# control_board_V2.net
KiCad netlist of a schematic drawn in EAGLE
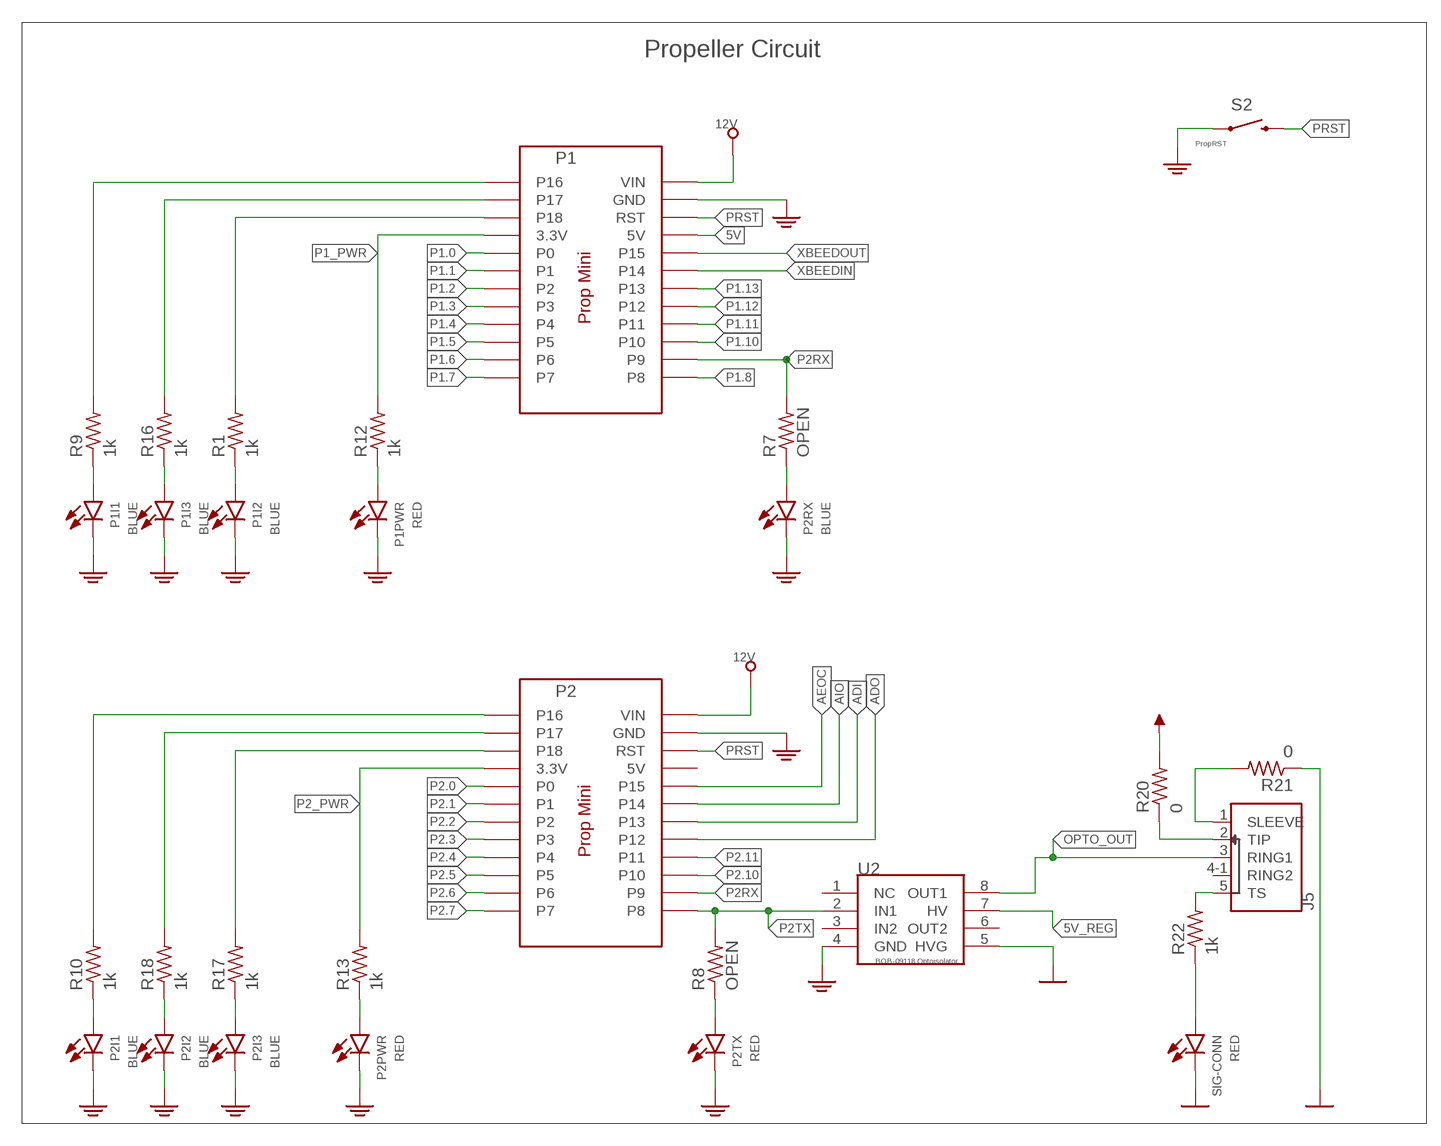
[diagram p0: schematic, sheet 1, part 1 of 2]
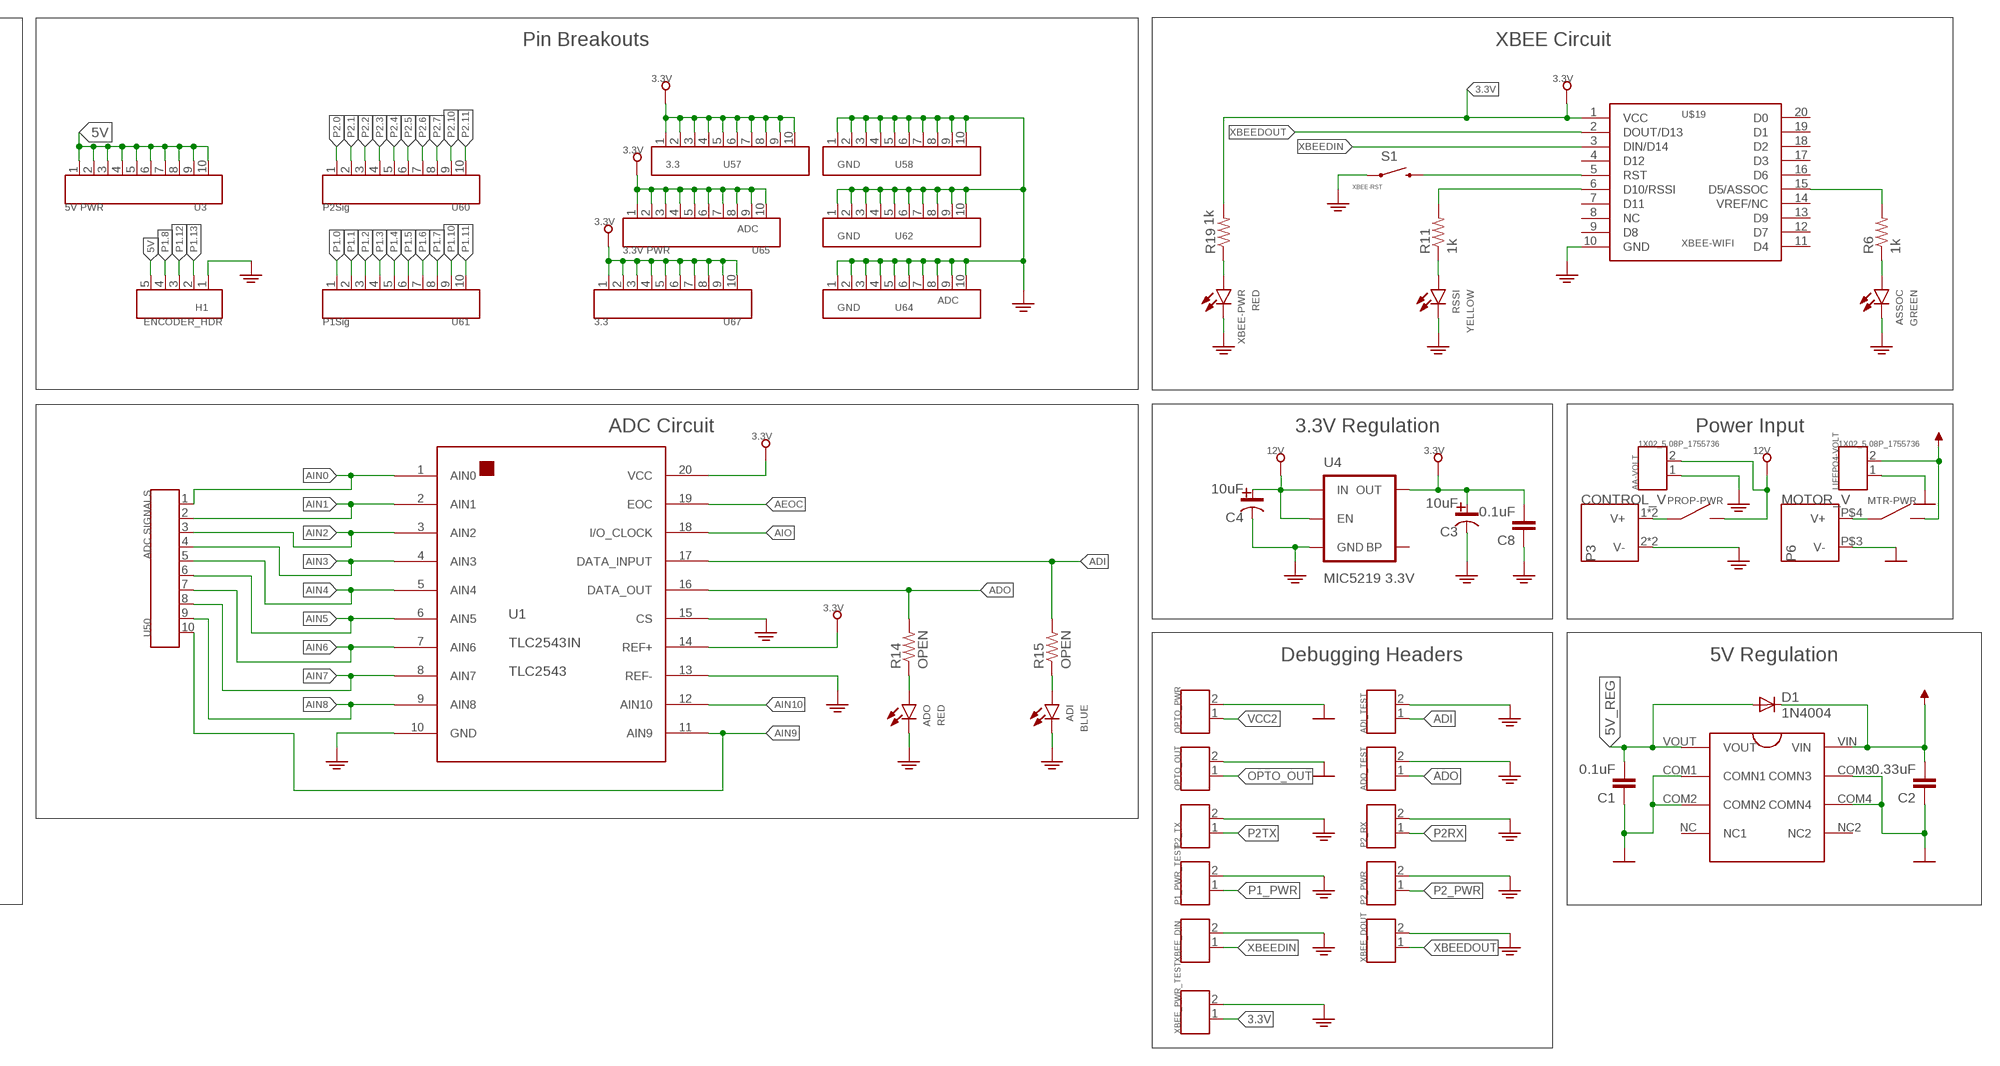
[diagram p1: schematic, sheet 1, part 2 of 2]

(export (version "E")
  (design (tool "Eeschema 10.0.6"))
  (components
    (comp (ref "AA-VOLT")
      (value "1X02_5.08P_1755736")
      (footprint "eagle-import:DIP5.08MM-1X02")
      (libsource (lib "eagle-import") (part "1X02_5.08P_1755736"))
    )
    (comp (ref "ADI")
      (value "BLUE")
      (footprint "eagle-import:0603")
      (libsource (lib "eagle-import") (part "LED-STD"))
    )
    (comp (ref "ADI_TEST")
      (value "1X02")
      (footprint "eagle-import:DIP0.1-1X02")
      (libsource (lib "eagle-import") (part "1X02"))
    )
    (comp (ref "ADO")
      (value "RED")
      (footprint "eagle-import:0603")
      (libsource (lib "eagle-import") (part "LED-STD"))
    )
    (comp (ref "ADO_TEST")
      (value "1X02")
      (footprint "eagle-import:DIP0.1-1X02")
      (libsource (lib "eagle-import") (part "1X02"))
    )
    (comp (ref "ASSOC")
      (value "GREEN")
      (footprint "eagle-import:0603")
      (libsource (lib "eagle-import") (part "LED-STD"))
    )
    (comp (ref "C1")
      (value "0.1uF")
      (footprint "eagle-import:0603")
      (libsource (lib "eagle-import") (part "C0603"))
    )
    (comp (ref "C2")
      (value "0.33uF")
      (footprint "eagle-import:0603")
      (libsource (lib "eagle-import") (part "C0603"))
    )
    (comp (ref "C3")
      (value "10uF")
      (footprint "eagle-import:0603-POL")
      (libsource (lib "eagle-import") (part "C-POL-T"))
    )
    (comp (ref "C4")
      (value "10uF")
      (footprint "eagle-import:0603-POL")
      (libsource (lib "eagle-import") (part "C-POL-T"))
    )
    (comp (ref "C8")
      (value "0.1uF")
      (footprint "eagle-import:0603")
      (libsource (lib "eagle-import") (part "C0603"))
    )
    (comp (ref "D1")
      (value "1N4004")
      (footprint "eagle-import:DO41-10")
      (libsource (lib "eagle-import") (part "1N4004"))
    )
    (comp (ref "H1")
      (value "ENCODER_HDR")
      (footprint "eagle-import:DIP0.1-1X05")
      (libsource (lib "eagle-import") (part "1X05"))
    )
    (comp (ref "J5")
      (value "SJ1-42535TS")
      (footprint "eagle-import:SJ1-42534-SMT")
      (libsource (lib "eagle-import") (part "SJ1-42535TS"))
    )
    (comp (ref "LIFEPO4-VOLT")
      (value "1X02_5.08P_1755736")
      (footprint "eagle-import:DIP5.08MM-1X02")
      (libsource (lib "eagle-import") (part "1X02_5.08P_1755736"))
    )
    (comp (ref "MTR-PWR")
      (value "A11JP")
      (footprint "eagle-import:NKK-SP-ASERIES")
      (libsource (lib "eagle-import") (part "A11JP"))
    )
    (comp (ref "OPTO_OUT")
      (value "1X02")
      (footprint "eagle-import:DIP0.1-1X02")
      (libsource (lib "eagle-import") (part "1X02"))
    )
    (comp (ref "OPTO_PWR")
      (value "1X02")
      (footprint "eagle-import:DIP0.1-1X02")
      (libsource (lib "eagle-import") (part "1X02"))
    )
    (comp (ref "P1")
      (value "PROP-MINI")
      (footprint "eagle-import:PROP-MINI")
      (libsource (lib "eagle-import") (part "PROP-MINI"))
    )
    (comp (ref "P1I1")
      (value "BLUE")
      (footprint "eagle-import:0603")
      (libsource (lib "eagle-import") (part "LED-STD"))
    )
    (comp (ref "P1I2")
      (value "BLUE")
      (footprint "eagle-import:0603")
      (libsource (lib "eagle-import") (part "LED-STD"))
    )
    (comp (ref "P1I3")
      (value "BLUE")
      (footprint "eagle-import:0603")
      (libsource (lib "eagle-import") (part "LED-STD"))
    )
    (comp (ref "P1PWR")
      (value "RED")
      (footprint "eagle-import:0603")
      (libsource (lib "eagle-import") (part "LED-STD"))
    )
    (comp (ref "P1_PWR_TEST")
      (value "1X02")
      (footprint "eagle-import:DIP0.1-1X02")
      (libsource (lib "eagle-import") (part "1X02"))
    )
    (comp (ref "P2")
      (value "PROP-MINI")
      (footprint "eagle-import:PROP-MINI")
      (libsource (lib "eagle-import") (part "PROP-MINI"))
    )
    (comp (ref "P2I1")
      (value "BLUE")
      (footprint "eagle-import:0603")
      (libsource (lib "eagle-import") (part "LED-STD"))
    )
    (comp (ref "P2I2")
      (value "BLUE")
      (footprint "eagle-import:0603")
      (libsource (lib "eagle-import") (part "LED-STD"))
    )
    (comp (ref "P2I3")
      (value "BLUE")
      (footprint "eagle-import:0603")
      (libsource (lib "eagle-import") (part "LED-STD"))
    )
    (comp (ref "P2PWR")
      (value "RED")
      (footprint "eagle-import:0603")
      (libsource (lib "eagle-import") (part "LED-STD"))
    )
    (comp (ref "P2RX")
      (value "BLUE")
      (footprint "eagle-import:0603")
      (libsource (lib "eagle-import") (part "LED-STD"))
    )
    (comp (ref "P2TX")
      (value "RED")
      (footprint "eagle-import:0603")
      (libsource (lib "eagle-import") (part "LED-STD"))
    )
    (comp (ref "P2_PWR")
      (value "1X02")
      (footprint "eagle-import:DIP0.1-1X02")
      (libsource (lib "eagle-import") (part "1X02"))
    )
    (comp (ref "P2_RX")
      (value "1X02")
      (footprint "eagle-import:DIP0.1-1X02")
      (libsource (lib "eagle-import") (part "1X02"))
    )
    (comp (ref "P2_TX")
      (value "1X02")
      (footprint "eagle-import:DIP0.1-1X02")
      (libsource (lib "eagle-import") (part "1X02"))
    )
    (comp (ref "P3")
      (value "CONTROL_V")
      (footprint "eagle-import:PJ-002BH-SMT-TR")
      (libsource (lib "eagle-import") (part "SINGLE-LINEPJ-014DH-SMT"))
    )
    (comp (ref "P6")
      (value "MOTOR_V")
      (footprint "eagle-import:PJ-037A")
      (libsource (lib "eagle-import") (part "SINGLE-LINE'"))
    )
    (comp (ref "PROP-PWR")
      (value "A11JP")
      (footprint "eagle-import:NKK-SP-ASERIES")
      (libsource (lib "eagle-import") (part "A11JP"))
    )
    (comp (ref "R1")
      (value "1k")
      (footprint "eagle-import:0603")
      (libsource (lib "eagle-import") (part "R0603"))
    )
    (comp (ref "R6")
      (value "1k")
      (footprint "eagle-import:0603")
      (libsource (lib "eagle-import") (part "R0603"))
    )
    (comp (ref "R7")
      (value "OPEN")
      (footprint "eagle-import:0603")
      (libsource (lib "eagle-import") (part "R0603"))
    )
    (comp (ref "R8")
      (value "OPEN")
      (footprint "eagle-import:0603")
      (libsource (lib "eagle-import") (part "R0603"))
    )
    (comp (ref "R9")
      (value "1k")
      (footprint "eagle-import:0603")
      (libsource (lib "eagle-import") (part "R0603"))
    )
    (comp (ref "R10")
      (value "1k")
      (footprint "eagle-import:0603")
      (libsource (lib "eagle-import") (part "R0603"))
    )
    (comp (ref "R11")
      (value "1k")
      (footprint "eagle-import:0603")
      (libsource (lib "eagle-import") (part "R0603"))
    )
    (comp (ref "R12")
      (value "1k")
      (footprint "eagle-import:0603")
      (libsource (lib "eagle-import") (part "R0603"))
    )
    (comp (ref "R13")
      (value "1k")
      (footprint "eagle-import:0603")
      (libsource (lib "eagle-import") (part "R0603"))
    )
    (comp (ref "R14")
      (value "OPEN")
      (footprint "eagle-import:0603")
      (libsource (lib "eagle-import") (part "R0603"))
    )
    (comp (ref "R15")
      (value "OPEN")
      (footprint "eagle-import:0603")
      (libsource (lib "eagle-import") (part "R0603"))
    )
    (comp (ref "R16")
      (value "1k")
      (footprint "eagle-import:0603")
      (libsource (lib "eagle-import") (part "R0603"))
    )
    (comp (ref "R17")
      (value "1k")
      (footprint "eagle-import:0603")
      (libsource (lib "eagle-import") (part "R0603"))
    )
    (comp (ref "R18")
      (value "1k")
      (footprint "eagle-import:0603")
      (libsource (lib "eagle-import") (part "R0603"))
    )
    (comp (ref "R19")
      (value "1k")
      (footprint "eagle-import:0603")
      (libsource (lib "eagle-import") (part "R0603"))
    )
    (comp (ref "R20")
      (value "0")
      (footprint "eagle-import:0603")
      (libsource (lib "eagle-import") (part "R0603"))
    )
    (comp (ref "R21")
      (value "0")
      (footprint "eagle-import:0603")
      (libsource (lib "eagle-import") (part "R0603"))
    )
    (comp (ref "R22")
      (value "1k")
      (footprint "eagle-import:0603")
      (libsource (lib "eagle-import") (part "R0603"))
    )
    (comp (ref "RSSI")
      (value "YELLOW")
      (footprint "eagle-import:0603")
      (libsource (lib "eagle-import") (part "LED-STD"))
    )
    (comp (ref "S1")
      (value "XBEE-RST")
      (footprint "eagle-import:TACTILE_SWITCH_SMD-2")
      (libsource (lib "eagle-import") (part "SWITCH-MOMENTARY-2SMD-2"))
    )
    (comp (ref "S2")
      (value "PropRST")
      (footprint "eagle-import:TACTILE_SWITCH_SMD-2")
      (libsource (lib "eagle-import") (part "SWITCH-MOMENTARY-2SMD-2"))
    )
    (comp (ref "SIG-CONN")
      (value "RED")
      (footprint "eagle-import:0603")
      (libsource (lib "eagle-import") (part "LED-STD"))
    )
    (comp (ref "U$19")
      (value "XBEE-WIFI")
      (footprint "eagle-import:XBEE-STD")
      (libsource (lib "eagle-import") (part "XBEE-WIFI"))
    )
    (comp (ref "U1")
      (value "TLC2543IN")
      (footprint "eagle-import:DIL-20")
      (libsource (lib "eagle-import") (part "TLC2543IN"))
    )
    (comp (ref "U2")
      (value "BOB-09118")
      (footprint "eagle-import:DIL08-0.1P-6W")
      (libsource (lib "eagle-import") (part "BOB-09118"))
    )
    (comp (ref "U3")
      (value "5V PWR")
      (footprint "eagle-import:DIP0.1-1X10")
      (libsource (lib "eagle-import") (part "1X10"))
    )
    (comp (ref "U4")
      (value "MIC5219 3.3V")
      (footprint "eagle-import:SOT23-5")
      (libsource (lib "eagle-import") (part "V_REG_MIC52193.3V"))
    )
    (comp (ref "U50")
      (value "ADC SIGNALS")
      (footprint "eagle-import:DIP0.1-1X10")
      (libsource (lib "eagle-import") (part "1X10"))
    )
    (comp (ref "U57")
      (value "3.3")
      (footprint "eagle-import:DIP0.1-1X10")
      (libsource (lib "eagle-import") (part "1X10"))
    )
    (comp (ref "U58")
      (value "GND")
      (footprint "eagle-import:DIP0.1-1X10")
      (libsource (lib "eagle-import") (part "1X10"))
    )
    (comp (ref "U60")
      (value "P2Sig")
      (footprint "eagle-import:DIP0.1-1X10")
      (libsource (lib "eagle-import") (part "1X10"))
    )
    (comp (ref "U61")
      (value "P1Sig")
      (footprint "eagle-import:DIP0.1-1X10")
      (libsource (lib "eagle-import") (part "1X10"))
    )
    (comp (ref "U62")
      (value "GND")
      (footprint "eagle-import:DIP0.1-1X10")
      (libsource (lib "eagle-import") (part "1X10"))
    )
    (comp (ref "U64")
      (value "GND")
      (footprint "eagle-import:DIP0.1-1X10")
      (libsource (lib "eagle-import") (part "1X10"))
    )
    (comp (ref "U65")
      (value "3.3V PWR")
      (footprint "eagle-import:DIP0.1-1X10")
      (libsource (lib "eagle-import") (part "1X10"))
    )
    (comp (ref "U67")
      (value "3.3")
      (footprint "eagle-import:DIP0.1-1X10")
      (libsource (lib "eagle-import") (part "1X10"))
    )
    (comp (ref "U70")
      (value "R-PDSO-G8")
      (footprint "eagle-import:UA78L05ACDR")
      (libsource (lib "eagle-import") (part "R-PDSO-G8"))
    )
    (comp (ref "XBEE-PWR")
      (value "RED")
      (footprint "eagle-import:0603")
      (libsource (lib "eagle-import") (part "LED-STD"))
    )
    (comp (ref "XBEE_DIN")
      (value "1X02")
      (footprint "eagle-import:DIP0.1-1X02")
      (libsource (lib "eagle-import") (part "1X02"))
    )
    (comp (ref "XBEE_DOUT")
      (value "1X02")
      (footprint "eagle-import:DIP0.1-1X02")
      (libsource (lib "eagle-import") (part "1X02"))
    )
    (comp (ref "XBEE_PWR_TEST")
      (value "1X02")
      (footprint "eagle-import:DIP0.1-1X02")
      (libsource (lib "eagle-import") (part "1X02"))
    )
  )
  (nets
    (net (code "1") (name "3.3V") (class "Default")
      (node (ref "C3") (pin "2") (pinfunction "2_2") (pintype "passive"))
      (node (ref "C8") (pin "2") (pinfunction "2_2") (pintype "passive"))
      (node (ref "R19") (pin "2") (pinfunction "P$2_2") (pintype "bidirectional"))
      (node (ref "U$19") (pin "1") (pinfunction "VCC_1") (pintype "bidirectional"))
      (node (ref "U1") (pin "14") (pinfunction "REF+_14") (pintype "bidirectional"))
      (node (ref "U1") (pin "20") (pinfunction "VCC_20") (pintype "bidirectional"))
      (node (ref "U4") (pin "5") (pinfunction "OUT_5") (pintype "passive"))
      (node (ref "U57") (pin "1") (pinfunction "1_1") (pintype "bidirectional"))
      (node (ref "U57") (pin "10") (pinfunction "10_10") (pintype "bidirectional"))
      (node (ref "U57") (pin "2") (pinfunction "2_2") (pintype "bidirectional"))
      (node (ref "U57") (pin "3") (pinfunction "3_3") (pintype "bidirectional"))
      (node (ref "U57") (pin "4") (pinfunction "4_4") (pintype "bidirectional"))
      (node (ref "U57") (pin "5") (pinfunction "5_5") (pintype "bidirectional"))
      (node (ref "U57") (pin "6") (pinfunction "6_6") (pintype "bidirectional"))
      (node (ref "U57") (pin "7") (pinfunction "7_7") (pintype "bidirectional"))
      (node (ref "U57") (pin "8") (pinfunction "8_8") (pintype "bidirectional"))
      (node (ref "U57") (pin "9") (pinfunction "9_9") (pintype "bidirectional"))
      (node (ref "U65") (pin "1") (pinfunction "1_1") (pintype "bidirectional"))
      (node (ref "U65") (pin "10") (pinfunction "10_10") (pintype "bidirectional"))
      (node (ref "U65") (pin "2") (pinfunction "2_2") (pintype "bidirectional"))
      (node (ref "U65") (pin "3") (pinfunction "3_3") (pintype "bidirectional"))
      (node (ref "U65") (pin "4") (pinfunction "4_4") (pintype "bidirectional"))
      (node (ref "U65") (pin "5") (pinfunction "5_5") (pintype "bidirectional"))
      (node (ref "U65") (pin "6") (pinfunction "6_6") (pintype "bidirectional"))
      (node (ref "U65") (pin "7") (pinfunction "7_7") (pintype "bidirectional"))
      (node (ref "U65") (pin "8") (pinfunction "8_8") (pintype "bidirectional"))
      (node (ref "U65") (pin "9") (pinfunction "9_9") (pintype "bidirectional"))
      (node (ref "U67") (pin "1") (pinfunction "1_1") (pintype "bidirectional"))
      (node (ref "U67") (pin "10") (pinfunction "10_10") (pintype "bidirectional"))
      (node (ref "U67") (pin "2") (pinfunction "2_2") (pintype "bidirectional"))
      (node (ref "U67") (pin "3") (pinfunction "3_3") (pintype "bidirectional"))
      (node (ref "U67") (pin "4") (pinfunction "4_4") (pintype "bidirectional"))
      (node (ref "U67") (pin "5") (pinfunction "5_5") (pintype "bidirectional"))
      (node (ref "U67") (pin "6") (pinfunction "6_6") (pintype "bidirectional"))
      (node (ref "U67") (pin "7") (pinfunction "7_7") (pintype "bidirectional"))
      (node (ref "U67") (pin "8") (pinfunction "8_8") (pintype "bidirectional"))
      (node (ref "U67") (pin "9") (pinfunction "9_9") (pintype "bidirectional"))
      (node (ref "XBEE_PWR_TEST") (pin "1") (pinfunction "1_1") (pintype "bidirectional"))
    )
    (net (code "2") (name "5V") (class "Default")
      (node (ref "H1") (pin "5") (pinfunction "5_5") (pintype "bidirectional"))
      (node (ref "P1") (pin "5V") (pinfunction "5V_5V") (pintype "bidirectional"))
      (node (ref "U3") (pin "1") (pinfunction "1_1") (pintype "bidirectional"))
      (node (ref "U3") (pin "10") (pinfunction "10_10") (pintype "bidirectional"))
      (node (ref "U3") (pin "2") (pinfunction "2_2") (pintype "bidirectional"))
      (node (ref "U3") (pin "3") (pinfunction "3_3") (pintype "bidirectional"))
      (node (ref "U3") (pin "4") (pinfunction "4_4") (pintype "bidirectional"))
      (node (ref "U3") (pin "5") (pinfunction "5_5") (pintype "bidirectional"))
      (node (ref "U3") (pin "6") (pinfunction "6_6") (pintype "bidirectional"))
      (node (ref "U3") (pin "7") (pinfunction "7_7") (pintype "bidirectional"))
      (node (ref "U3") (pin "8") (pinfunction "8_8") (pintype "bidirectional"))
      (node (ref "U3") (pin "9") (pinfunction "9_9") (pintype "bidirectional"))
    )
    (net (code "3") (name "5V_REG") (class "Default")
      (node (ref "C1") (pin "2") (pinfunction "2_2") (pintype "passive"))
      (node (ref "D1") (pin "A") (pinfunction "A_A") (pintype "passive"))
      (node (ref "U2") (pin "7") (pinfunction "HV_7") (pintype "bidirectional"))
      (node (ref "U70") (pin "VOUT") (pinfunction "VOUT_VOUT") (pintype "bidirectional"))
    )
    (net (code "4") (name "12V") (class "Default")
      (node (ref "AA-VOLT") (pin "2") (pinfunction "2_2") (pintype "bidirectional"))
      (node (ref "C4") (pin "2") (pinfunction "2_2") (pintype "passive"))
      (node (ref "P1") (pin "VIN") (pinfunction "VIN_VIN") (pintype "bidirectional"))
      (node (ref "P2") (pin "VIN") (pinfunction "VIN_VIN") (pintype "bidirectional"))
      (node (ref "PROP-PWR") (pin "3") (pinfunction "2_3") (pintype "bidirectional"))
      (node (ref "U4") (pin "1") (pinfunction "IN_1") (pintype "input"))
      (node (ref "U4") (pin "3") (pinfunction "EN_3") (pintype "input"))
    )
    (net (code "5") (name "ADI") (class "Default")
      (node (ref "ADI_TEST") (pin "1") (pinfunction "1_1") (pintype "bidirectional"))
      (node (ref "P2") (pin "P13") (pinfunction "P13_P13") (pintype "bidirectional"))
      (node (ref "R15") (pin "2") (pinfunction "P$2_2") (pintype "bidirectional"))
      (node (ref "U1") (pin "17") (pinfunction "DATA_INPUT_17") (pintype "bidirectional"))
    )
    (net (code "6") (name "ADO") (class "Default")
      (node (ref "ADO_TEST") (pin "1") (pinfunction "1_1") (pintype "bidirectional"))
      (node (ref "P2") (pin "P12") (pinfunction "P12_P12") (pintype "bidirectional"))
      (node (ref "R14") (pin "2") (pinfunction "P$2_2") (pintype "bidirectional"))
      (node (ref "U1") (pin "16") (pinfunction "DATA_OUT_16") (pintype "bidirectional"))
    )
    (net (code "7") (name "AEOC") (class "Default")
      (node (ref "P2") (pin "P15") (pinfunction "P15_P15") (pintype "bidirectional"))
      (node (ref "U1") (pin "19") (pinfunction "EOC_19") (pintype "bidirectional"))
    )
    (net (code "8") (name "AIN0") (class "Default")
      (node (ref "U1") (pin "1") (pinfunction "AIN0_1") (pintype "bidirectional"))
      (node (ref "U50") (pin "1") (pinfunction "1_1") (pintype "bidirectional"))
    )
    (net (code "9") (name "AIN1") (class "Default")
      (node (ref "U1") (pin "2") (pinfunction "AIN1_2") (pintype "bidirectional"))
      (node (ref "U50") (pin "2") (pinfunction "2_2") (pintype "bidirectional"))
    )
    (net (code "10") (name "AIN2") (class "Default")
      (node (ref "U1") (pin "3") (pinfunction "AIN2_3") (pintype "bidirectional"))
      (node (ref "U50") (pin "3") (pinfunction "3_3") (pintype "bidirectional"))
    )
    (net (code "11") (name "AIN3") (class "Default")
      (node (ref "U1") (pin "4") (pinfunction "AIN3_4") (pintype "bidirectional"))
      (node (ref "U50") (pin "4") (pinfunction "4_4") (pintype "bidirectional"))
    )
    (net (code "12") (name "AIN4") (class "Default")
      (node (ref "U1") (pin "5") (pinfunction "AIN4_5") (pintype "bidirectional"))
      (node (ref "U50") (pin "5") (pinfunction "5_5") (pintype "bidirectional"))
    )
    (net (code "13") (name "AIN5") (class "Default")
      (node (ref "U1") (pin "6") (pinfunction "AIN5_6") (pintype "bidirectional"))
      (node (ref "U50") (pin "6") (pinfunction "6_6") (pintype "bidirectional"))
    )
    (net (code "14") (name "AIN6") (class "Default")
      (node (ref "U1") (pin "7") (pinfunction "AIN6_7") (pintype "bidirectional"))
      (node (ref "U50") (pin "7") (pinfunction "7_7") (pintype "bidirectional"))
    )
    (net (code "15") (name "AIN7") (class "Default")
      (node (ref "U1") (pin "8") (pinfunction "AIN7_8") (pintype "bidirectional"))
      (node (ref "U50") (pin "8") (pinfunction "8_8") (pintype "bidirectional"))
    )
    (net (code "16") (name "AIN8") (class "Default")
      (node (ref "U1") (pin "9") (pinfunction "AIN8_9") (pintype "bidirectional"))
      (node (ref "U50") (pin "9") (pinfunction "9_9") (pintype "bidirectional"))
    )
    (net (code "17") (name "AIN9") (class "Default")
      (node (ref "U1") (pin "11") (pinfunction "AIN9_11") (pintype "bidirectional"))
      (node (ref "U50") (pin "10") (pinfunction "10_10") (pintype "bidirectional"))
    )
    (net (code "18") (name "AIN10") (class "Default")
      (node (ref "U1") (pin "12") (pinfunction "AIN10_12") (pintype "bidirectional"))
    )
    (net (code "19") (name "AIO") (class "Default")
      (node (ref "P2") (pin "P14") (pinfunction "P14_P14") (pintype "bidirectional"))
      (node (ref "U1") (pin "18") (pinfunction "I/O_CLOCK_18") (pintype "bidirectional"))
    )
    (net (code "20") (name "GND") (class "Default")
      (node (ref "AA-VOLT") (pin "1") (pinfunction "1_1") (pintype "bidirectional"))
      (node (ref "ADI") (pin "OUT") (pinfunction "OUT_OUT") (pintype "bidirectional"))
      (node (ref "ADI_TEST") (pin "2") (pinfunction "2_2") (pintype "bidirectional"))
      (node (ref "ADO") (pin "OUT") (pinfunction "OUT_OUT") (pintype "bidirectional"))
      (node (ref "ADO_TEST") (pin "2") (pinfunction "2_2") (pintype "bidirectional"))
      (node (ref "ASSOC") (pin "OUT") (pinfunction "OUT_OUT") (pintype "bidirectional"))
      (node (ref "C3") (pin "1") (pinfunction "1_1") (pintype "passive"))
      (node (ref "C4") (pin "1") (pinfunction "1_1") (pintype "passive"))
      (node (ref "C8") (pin "1") (pinfunction "1_1") (pintype "passive"))
      (node (ref "H1") (pin "1") (pinfunction "1_1") (pintype "bidirectional"))
      (node (ref "P1") (pin "GND") (pinfunction "GND_GND") (pintype "bidirectional"))
      (node (ref "P1I1") (pin "OUT") (pinfunction "OUT_OUT") (pintype "bidirectional"))
      (node (ref "P1I2") (pin "OUT") (pinfunction "OUT_OUT") (pintype "bidirectional"))
      (node (ref "P1I3") (pin "OUT") (pinfunction "OUT_OUT") (pintype "bidirectional"))
      (node (ref "P1PWR") (pin "OUT") (pinfunction "OUT_OUT") (pintype "bidirectional"))
      (node (ref "P1_PWR_TEST") (pin "2") (pinfunction "2_2") (pintype "bidirectional"))
      (node (ref "P2") (pin "GND") (pinfunction "GND_GND") (pintype "bidirectional"))
      (node (ref "P2I1") (pin "OUT") (pinfunction "OUT_OUT") (pintype "bidirectional"))
      (node (ref "P2I2") (pin "OUT") (pinfunction "OUT_OUT") (pintype "bidirectional"))
      (node (ref "P2I3") (pin "OUT") (pinfunction "OUT_OUT") (pintype "bidirectional"))
      (node (ref "P2PWR") (pin "OUT") (pinfunction "OUT_OUT") (pintype "bidirectional"))
      (node (ref "P2RX") (pin "OUT") (pinfunction "OUT_OUT") (pintype "bidirectional"))
      (node (ref "P2TX") (pin "OUT") (pinfunction "OUT_OUT") (pintype "bidirectional"))
      (node (ref "P2_PWR") (pin "2") (pinfunction "2_2") (pintype "bidirectional"))
      (node (ref "P2_RX") (pin "2") (pinfunction "2_2") (pintype "bidirectional"))
      (node (ref "P2_TX") (pin "2") (pinfunction "2_2") (pintype "bidirectional"))
      (node (ref "P3") (pin "2") (pinfunction "V-_2") (pintype "bidirectional"))
      (node (ref "P3") (pin "3") (pinfunction "V-_3") (pintype "bidirectional"))
      (node (ref "RSSI") (pin "OUT") (pinfunction "OUT_OUT") (pintype "bidirectional"))
      (node (ref "S1") (pin "2") (pinfunction "1_2") (pintype "passive"))
      (node (ref "S2") (pin "2") (pinfunction "1_2") (pintype "passive"))
      (node (ref "U$19") (pin "10") (pinfunction "GND_10") (pintype "bidirectional"))
      (node (ref "U1") (pin "10") (pinfunction "GND_10") (pintype "bidirectional"))
      (node (ref "U1") (pin "13") (pinfunction "REF-_13") (pintype "bidirectional"))
      (node (ref "U1") (pin "15") (pinfunction "CS_15") (pintype "bidirectional"))
      (node (ref "U2") (pin "4") (pinfunction "GND_4") (pintype "bidirectional"))
      (node (ref "U4") (pin "2") (pinfunction "GND_2") (pintype "input"))
      (node (ref "U58") (pin "1") (pinfunction "1_1") (pintype "bidirectional"))
      (node (ref "U58") (pin "10") (pinfunction "10_10") (pintype "bidirectional"))
      (node (ref "U58") (pin "2") (pinfunction "2_2") (pintype "bidirectional"))
      (node (ref "U58") (pin "3") (pinfunction "3_3") (pintype "bidirectional"))
      (node (ref "U58") (pin "4") (pinfunction "4_4") (pintype "bidirectional"))
      (node (ref "U58") (pin "5") (pinfunction "5_5") (pintype "bidirectional"))
      (node (ref "U58") (pin "6") (pinfunction "6_6") (pintype "bidirectional"))
      (node (ref "U58") (pin "7") (pinfunction "7_7") (pintype "bidirectional"))
      (node (ref "U58") (pin "8") (pinfunction "8_8") (pintype "bidirectional"))
      (node (ref "U58") (pin "9") (pinfunction "9_9") (pintype "bidirectional"))
      (node (ref "U62") (pin "1") (pinfunction "1_1") (pintype "bidirectional"))
      (node (ref "U62") (pin "10") (pinfunction "10_10") (pintype "bidirectional"))
      (node (ref "U62") (pin "2") (pinfunction "2_2") (pintype "bidirectional"))
      (node (ref "U62") (pin "3") (pinfunction "3_3") (pintype "bidirectional"))
      (node (ref "U62") (pin "4") (pinfunction "4_4") (pintype "bidirectional"))
      (node (ref "U62") (pin "5") (pinfunction "5_5") (pintype "bidirectional"))
      (node (ref "U62") (pin "6") (pinfunction "6_6") (pintype "bidirectional"))
      (node (ref "U62") (pin "7") (pinfunction "7_7") (pintype "bidirectional"))
      (node (ref "U62") (pin "8") (pinfunction "8_8") (pintype "bidirectional"))
      (node (ref "U62") (pin "9") (pinfunction "9_9") (pintype "bidirectional"))
      (node (ref "U64") (pin "1") (pinfunction "1_1") (pintype "bidirectional"))
      (node (ref "U64") (pin "10") (pinfunction "10_10") (pintype "bidirectional"))
      (node (ref "U64") (pin "2") (pinfunction "2_2") (pintype "bidirectional"))
      (node (ref "U64") (pin "3") (pinfunction "3_3") (pintype "bidirectional"))
      (node (ref "U64") (pin "4") (pinfunction "4_4") (pintype "bidirectional"))
      (node (ref "U64") (pin "5") (pinfunction "5_5") (pintype "bidirectional"))
      (node (ref "U64") (pin "6") (pinfunction "6_6") (pintype "bidirectional"))
      (node (ref "U64") (pin "7") (pinfunction "7_7") (pintype "bidirectional"))
      (node (ref "U64") (pin "8") (pinfunction "8_8") (pintype "bidirectional"))
      (node (ref "U64") (pin "9") (pinfunction "9_9") (pintype "bidirectional"))
      (node (ref "XBEE-PWR") (pin "OUT") (pinfunction "OUT_OUT") (pintype "bidirectional"))
      (node (ref "XBEE_DIN") (pin "2") (pinfunction "2_2") (pintype "bidirectional"))
      (node (ref "XBEE_DOUT") (pin "2") (pinfunction "2_2") (pintype "bidirectional"))
      (node (ref "XBEE_PWR_TEST") (pin "2") (pinfunction "2_2") (pintype "bidirectional"))
    )
    (net (code "21") (name "GND2") (class "Default")
      (node (ref "C1") (pin "1") (pinfunction "1_1") (pintype "passive"))
      (node (ref "C2") (pin "1") (pinfunction "1_1") (pintype "passive"))
      (node (ref "LIFEPO4-VOLT") (pin "1") (pinfunction "1_1") (pintype "bidirectional"))
      (node (ref "OPTO_OUT") (pin "2") (pinfunction "2_2") (pintype "bidirectional"))
      (node (ref "OPTO_PWR") (pin "2") (pinfunction "2_2") (pintype "bidirectional"))
      (node (ref "P6") (pin "P$3") (pinfunction "V-_P$3") (pintype "bidirectional"))
      (node (ref "R21") (pin "1") (pinfunction "P$1_1") (pintype "bidirectional"))
      (node (ref "SIG-CONN") (pin "OUT") (pinfunction "OUT_OUT") (pintype "bidirectional"))
      (node (ref "U2") (pin "5") (pinfunction "HVG_5") (pintype "bidirectional"))
      (node (ref "U70") (pin "COM1") (pinfunction "COMN1_COM1") (pintype "bidirectional"))
      (node (ref "U70") (pin "COM2") (pinfunction "COMN2_COM2") (pintype "bidirectional"))
      (node (ref "U70") (pin "COM3") (pinfunction "COMN3_COM3") (pintype "bidirectional"))
      (node (ref "U70") (pin "COM4") (pinfunction "COMN4_COM4") (pintype "bidirectional"))
    )
    (net (code "22") (name "Net-(J5-SLEEVE)") (class "Default")
      (node (ref "J5") (pin "1") (pinfunction "SLEEVE_1") (pintype "bidirectional"))
      (node (ref "R21") (pin "2") (pinfunction "P$2_2") (pintype "bidirectional"))
    )
    (net (code "23") (name "Net-(J5-TIP)") (class "Default")
      (node (ref "J5") (pin "2") (pinfunction "TIP_2") (pintype "bidirectional"))
      (node (ref "R20") (pin "1") (pinfunction "P$1_1") (pintype "bidirectional"))
    )
    (net (code "24") (name "Net-(J5-TS)") (class "Default")
      (node (ref "J5") (pin "5") (pinfunction "TS_5") (pintype "bidirectional"))
      (node (ref "R22") (pin "2") (pinfunction "P$2_2") (pintype "bidirectional"))
    )
    (net (code "25") (name "Net-(P3-V+-Pad1)") (class "Default")
      (node (ref "P3") (pin "1") (pinfunction "V+_1") (pintype "bidirectional"))
      (node (ref "P3") (pin "1.") (pinfunction "V+_1.") (pintype "bidirectional"))
      (node (ref "PROP-PWR") (pin "1") (pinfunction "1_1") (pintype "bidirectional"))
    )
    (net (code "26") (name "Net-(P6-V+)") (class "Default")
      (node (ref "MTR-PWR") (pin "1") (pinfunction "1_1") (pintype "bidirectional"))
      (node (ref "P6") (pin "P$4") (pinfunction "V+_P$4") (pintype "bidirectional"))
    )
    (net (code "27") (name "Net-(R1-P$1)") (class "Default")
      (node (ref "P1I2") (pin "IN") (pinfunction "IN_IN") (pintype "bidirectional"))
      (node (ref "R1") (pin "1") (pinfunction "P$1_1") (pintype "bidirectional"))
    )
    (net (code "28") (name "Net-(R1-P$2)") (class "Default")
      (node (ref "P1") (pin "P18") (pinfunction "P18_P18") (pintype "bidirectional"))
      (node (ref "R1") (pin "2") (pinfunction "P$2_2") (pintype "bidirectional"))
    )
    (net (code "29") (name "Net-(R6-P$1)") (class "Default")
      (node (ref "ASSOC") (pin "IN") (pinfunction "IN_IN") (pintype "bidirectional"))
      (node (ref "R6") (pin "1") (pinfunction "P$1_1") (pintype "bidirectional"))
    )
    (net (code "30") (name "Net-(R6-P$2)") (class "Default")
      (node (ref "R6") (pin "2") (pinfunction "P$2_2") (pintype "bidirectional"))
      (node (ref "U$19") (pin "15") (pinfunction "D5/ASSOC_15") (pintype "bidirectional"))
    )
    (net (code "31") (name "Net-(R7-P$1)") (class "Default")
      (node (ref "P2RX") (pin "IN") (pinfunction "IN_IN") (pintype "bidirectional"))
      (node (ref "R7") (pin "1") (pinfunction "P$1_1") (pintype "bidirectional"))
    )
    (net (code "32") (name "Net-(R8-P$1)") (class "Default")
      (node (ref "P2TX") (pin "IN") (pinfunction "IN_IN") (pintype "bidirectional"))
      (node (ref "R8") (pin "1") (pinfunction "P$1_1") (pintype "bidirectional"))
    )
    (net (code "33") (name "Net-(R9-P$1)") (class "Default")
      (node (ref "P1I1") (pin "IN") (pinfunction "IN_IN") (pintype "bidirectional"))
      (node (ref "R9") (pin "1") (pinfunction "P$1_1") (pintype "bidirectional"))
    )
    (net (code "34") (name "Net-(R9-P$2)") (class "Default")
      (node (ref "P1") (pin "P16") (pinfunction "P16_P16") (pintype "bidirectional"))
      (node (ref "R9") (pin "2") (pinfunction "P$2_2") (pintype "bidirectional"))
    )
    (net (code "35") (name "Net-(R10-P$1)") (class "Default")
      (node (ref "P2I1") (pin "IN") (pinfunction "IN_IN") (pintype "bidirectional"))
      (node (ref "R10") (pin "1") (pinfunction "P$1_1") (pintype "bidirectional"))
    )
    (net (code "36") (name "Net-(R10-P$2)") (class "Default")
      (node (ref "P2") (pin "P16") (pinfunction "P16_P16") (pintype "bidirectional"))
      (node (ref "R10") (pin "2") (pinfunction "P$2_2") (pintype "bidirectional"))
    )
    (net (code "37") (name "Net-(R11-P$1)") (class "Default")
      (node (ref "R11") (pin "1") (pinfunction "P$1_1") (pintype "bidirectional"))
      (node (ref "RSSI") (pin "IN") (pinfunction "IN_IN") (pintype "bidirectional"))
    )
    (net (code "38") (name "Net-(R11-P$2)") (class "Default")
      (node (ref "R11") (pin "2") (pinfunction "P$2_2") (pintype "bidirectional"))
      (node (ref "U$19") (pin "6") (pinfunction "D10/RSSI_6") (pintype "bidirectional"))
    )
    (net (code "39") (name "Net-(R12-P$1)") (class "Default")
      (node (ref "P1PWR") (pin "IN") (pinfunction "IN_IN") (pintype "bidirectional"))
      (node (ref "R12") (pin "1") (pinfunction "P$1_1") (pintype "bidirectional"))
    )
    (net (code "40") (name "Net-(R13-P$1)") (class "Default")
      (node (ref "P2PWR") (pin "IN") (pinfunction "IN_IN") (pintype "bidirectional"))
      (node (ref "R13") (pin "1") (pinfunction "P$1_1") (pintype "bidirectional"))
    )
    (net (code "41") (name "Net-(R14-P$1)") (class "Default")
      (node (ref "ADO") (pin "IN") (pinfunction "IN_IN") (pintype "bidirectional"))
      (node (ref "R14") (pin "1") (pinfunction "P$1_1") (pintype "bidirectional"))
    )
    (net (code "42") (name "Net-(R15-P$1)") (class "Default")
      (node (ref "ADI") (pin "IN") (pinfunction "IN_IN") (pintype "bidirectional"))
      (node (ref "R15") (pin "1") (pinfunction "P$1_1") (pintype "bidirectional"))
    )
    (net (code "43") (name "Net-(R16-P$1)") (class "Default")
      (node (ref "P1I3") (pin "IN") (pinfunction "IN_IN") (pintype "bidirectional"))
      (node (ref "R16") (pin "1") (pinfunction "P$1_1") (pintype "bidirectional"))
    )
    (net (code "44") (name "Net-(R16-P$2)") (class "Default")
      (node (ref "P1") (pin "P17") (pinfunction "P17_P17") (pintype "bidirectional"))
      (node (ref "R16") (pin "2") (pinfunction "P$2_2") (pintype "bidirectional"))
    )
    (net (code "45") (name "Net-(R17-P$1)") (class "Default")
      (node (ref "P2I3") (pin "IN") (pinfunction "IN_IN") (pintype "bidirectional"))
      (node (ref "R17") (pin "1") (pinfunction "P$1_1") (pintype "bidirectional"))
    )
    (net (code "46") (name "Net-(R17-P$2)") (class "Default")
      (node (ref "P2") (pin "P18") (pinfunction "P18_P18") (pintype "bidirectional"))
      (node (ref "R17") (pin "2") (pinfunction "P$2_2") (pintype "bidirectional"))
    )
    (net (code "47") (name "Net-(R18-P$1)") (class "Default")
      (node (ref "P2I2") (pin "IN") (pinfunction "IN_IN") (pintype "bidirectional"))
      (node (ref "R18") (pin "1") (pinfunction "P$1_1") (pintype "bidirectional"))
    )
    (net (code "48") (name "Net-(R18-P$2)") (class "Default")
      (node (ref "P2") (pin "P17") (pinfunction "P17_P17") (pintype "bidirectional"))
      (node (ref "R18") (pin "2") (pinfunction "P$2_2") (pintype "bidirectional"))
    )
    (net (code "49") (name "Net-(R19-P$1)") (class "Default")
      (node (ref "R19") (pin "1") (pinfunction "P$1_1") (pintype "bidirectional"))
      (node (ref "XBEE-PWR") (pin "IN") (pinfunction "IN_IN") (pintype "bidirectional"))
    )
    (net (code "50") (name "Net-(R22-P$1)") (class "Default")
      (node (ref "R22") (pin "1") (pinfunction "P$1_1") (pintype "bidirectional"))
      (node (ref "SIG-CONN") (pin "IN") (pinfunction "IN_IN") (pintype "bidirectional"))
    )
    (net (code "51") (name "Net-(S1-2)") (class "Default")
      (node (ref "S1") (pin "1") (pinfunction "2_1") (pintype "passive"))
      (node (ref "U$19") (pin "5") (pinfunction "RST_5") (pintype "bidirectional"))
    )
    (net (code "52") (name "OPTO_OUT") (class "Default")
      (node (ref "J5") (pin "3") (pinfunction "RING1_3") (pintype "bidirectional"))
      (node (ref "OPTO_OUT") (pin "1") (pinfunction "1_1") (pintype "bidirectional"))
      (node (ref "U2") (pin "8") (pinfunction "OUT1_8") (pintype "bidirectional"))
    )
    (net (code "53") (name "P1.0") (class "Default")
      (node (ref "P1") (pin "P0") (pinfunction "P0_P0") (pintype "bidirectional"))
      (node (ref "U61") (pin "1") (pinfunction "1_1") (pintype "bidirectional"))
    )
    (net (code "54") (name "P1.1") (class "Default")
      (node (ref "P1") (pin "P1") (pinfunction "P1_P1") (pintype "bidirectional"))
      (node (ref "U61") (pin "2") (pinfunction "2_2") (pintype "bidirectional"))
    )
    (net (code "55") (name "P1.2") (class "Default")
      (node (ref "P1") (pin "P2") (pinfunction "P2_P2") (pintype "bidirectional"))
      (node (ref "U61") (pin "3") (pinfunction "3_3") (pintype "bidirectional"))
    )
    (net (code "56") (name "P1.3") (class "Default")
      (node (ref "P1") (pin "P3") (pinfunction "P3_P3") (pintype "bidirectional"))
      (node (ref "U61") (pin "4") (pinfunction "4_4") (pintype "bidirectional"))
    )
    (net (code "57") (name "P1.4") (class "Default")
      (node (ref "P1") (pin "P4") (pinfunction "P4_P4") (pintype "bidirectional"))
      (node (ref "U61") (pin "5") (pinfunction "5_5") (pintype "bidirectional"))
    )
    (net (code "58") (name "P1.5") (class "Default")
      (node (ref "P1") (pin "P5") (pinfunction "P5_P5") (pintype "bidirectional"))
      (node (ref "U61") (pin "6") (pinfunction "6_6") (pintype "bidirectional"))
    )
    (net (code "59") (name "P1.6") (class "Default")
      (node (ref "P1") (pin "P6") (pinfunction "P6_P6") (pintype "bidirectional"))
      (node (ref "U61") (pin "7") (pinfunction "7_7") (pintype "bidirectional"))
    )
    (net (code "60") (name "P1.7") (class "Default")
      (node (ref "P1") (pin "P7") (pinfunction "P7_P7") (pintype "bidirectional"))
      (node (ref "U61") (pin "8") (pinfunction "8_8") (pintype "bidirectional"))
    )
    (net (code "61") (name "P1.8") (class "Default")
      (node (ref "H1") (pin "4") (pinfunction "4_4") (pintype "bidirectional"))
      (node (ref "P1") (pin "P8") (pinfunction "P8_P8") (pintype "bidirectional"))
    )
    (net (code "62") (name "P1.10") (class "Default")
      (node (ref "P1") (pin "P10") (pinfunction "P10_P10") (pintype "bidirectional"))
      (node (ref "U61") (pin "9") (pinfunction "9_9") (pintype "bidirectional"))
    )
    (net (code "63") (name "P1.11") (class "Default")
      (node (ref "P1") (pin "P11") (pinfunction "P11_P11") (pintype "bidirectional"))
      (node (ref "U61") (pin "10") (pinfunction "10_10") (pintype "bidirectional"))
    )
    (net (code "64") (name "P1.12") (class "Default")
      (node (ref "H1") (pin "3") (pinfunction "3_3") (pintype "bidirectional"))
      (node (ref "P1") (pin "P12") (pinfunction "P12_P12") (pintype "bidirectional"))
    )
    (net (code "65") (name "P1.13") (class "Default")
      (node (ref "H1") (pin "2") (pinfunction "2_2") (pintype "bidirectional"))
      (node (ref "P1") (pin "P13") (pinfunction "P13_P13") (pintype "bidirectional"))
    )
    (net (code "66") (name "P1_PWR") (class "Default")
      (node (ref "P1") (pin "3.3V") (pinfunction "3.3V_3.3V") (pintype "bidirectional"))
      (node (ref "P1_PWR_TEST") (pin "1") (pinfunction "1_1") (pintype "bidirectional"))
      (node (ref "R12") (pin "2") (pinfunction "P$2_2") (pintype "bidirectional"))
    )
    (net (code "67") (name "P2.0") (class "Default")
      (node (ref "P2") (pin "P0") (pinfunction "P0_P0") (pintype "bidirectional"))
      (node (ref "U60") (pin "1") (pinfunction "1_1") (pintype "bidirectional"))
    )
    (net (code "68") (name "P2.1") (class "Default")
      (node (ref "P2") (pin "P1") (pinfunction "P1_P1") (pintype "bidirectional"))
      (node (ref "U60") (pin "2") (pinfunction "2_2") (pintype "bidirectional"))
    )
    (net (code "69") (name "P2.2") (class "Default")
      (node (ref "P2") (pin "P2") (pinfunction "P2_P2") (pintype "bidirectional"))
      (node (ref "U60") (pin "3") (pinfunction "3_3") (pintype "bidirectional"))
    )
    (net (code "70") (name "P2.3") (class "Default")
      (node (ref "P2") (pin "P3") (pinfunction "P3_P3") (pintype "bidirectional"))
      (node (ref "U60") (pin "4") (pinfunction "4_4") (pintype "bidirectional"))
    )
    (net (code "71") (name "P2.4") (class "Default")
      (node (ref "P2") (pin "P4") (pinfunction "P4_P4") (pintype "bidirectional"))
      (node (ref "U60") (pin "5") (pinfunction "5_5") (pintype "bidirectional"))
    )
    (net (code "72") (name "P2.5") (class "Default")
      (node (ref "P2") (pin "P5") (pinfunction "P5_P5") (pintype "bidirectional"))
      (node (ref "U60") (pin "6") (pinfunction "6_6") (pintype "bidirectional"))
    )
    (net (code "73") (name "P2.6") (class "Default")
      (node (ref "P2") (pin "P6") (pinfunction "P6_P6") (pintype "bidirectional"))
      (node (ref "U60") (pin "7") (pinfunction "7_7") (pintype "bidirectional"))
    )
    (net (code "74") (name "P2.7") (class "Default")
      (node (ref "P2") (pin "P7") (pinfunction "P7_P7") (pintype "bidirectional"))
      (node (ref "U60") (pin "8") (pinfunction "8_8") (pintype "bidirectional"))
    )
    (net (code "75") (name "P2.10") (class "Default")
      (node (ref "P2") (pin "P10") (pinfunction "P10_P10") (pintype "bidirectional"))
      (node (ref "U60") (pin "9") (pinfunction "9_9") (pintype "bidirectional"))
    )
    (net (code "76") (name "P2.11") (class "Default")
      (node (ref "P2") (pin "P11") (pinfunction "P11_P11") (pintype "bidirectional"))
      (node (ref "U60") (pin "10") (pinfunction "10_10") (pintype "bidirectional"))
    )
    (net (code "77") (name "P2RX") (class "Default")
      (node (ref "P1") (pin "P9") (pinfunction "P9_P9") (pintype "bidirectional"))
      (node (ref "P2") (pin "P9") (pinfunction "P9_P9") (pintype "bidirectional"))
      (node (ref "P2_RX") (pin "1") (pinfunction "1_1") (pintype "bidirectional"))
      (node (ref "R7") (pin "2") (pinfunction "P$2_2") (pintype "bidirectional"))
    )
    (net (code "78") (name "P2TX") (class "Default")
      (node (ref "P2") (pin "P8") (pinfunction "P8_P8") (pintype "bidirectional"))
      (node (ref "P2_TX") (pin "1") (pinfunction "1_1") (pintype "bidirectional"))
      (node (ref "R8") (pin "2") (pinfunction "P$2_2") (pintype "bidirectional"))
      (node (ref "U2") (pin "2") (pinfunction "IN1_2") (pintype "bidirectional"))
    )
    (net (code "79") (name "P2_PWR") (class "Default")
      (node (ref "P2") (pin "3.3V") (pinfunction "3.3V_3.3V") (pintype "bidirectional"))
      (node (ref "P2_PWR") (pin "1") (pinfunction "1_1") (pintype "bidirectional"))
      (node (ref "R13") (pin "2") (pinfunction "P$2_2") (pintype "bidirectional"))
    )
    (net (code "80") (name "PRST") (class "Default")
      (node (ref "P1") (pin "RST") (pinfunction "RST_RST") (pintype "bidirectional"))
      (node (ref "P2") (pin "RST") (pinfunction "RST_RST") (pintype "bidirectional"))
      (node (ref "S2") (pin "1") (pinfunction "2_1") (pintype "passive"))
    )
    (net (code "81") (name "VCC2") (class "Default")
      (node (ref "C2") (pin "2") (pinfunction "2_2") (pintype "passive"))
      (node (ref "D1") (pin "C") (pinfunction "C_C") (pintype "passive"))
      (node (ref "LIFEPO4-VOLT") (pin "2") (pinfunction "2_2") (pintype "bidirectional"))
      (node (ref "MTR-PWR") (pin "3") (pinfunction "2_3") (pintype "bidirectional"))
      (node (ref "OPTO_PWR") (pin "1") (pinfunction "1_1") (pintype "bidirectional"))
      (node (ref "R20") (pin "2") (pinfunction "P$2_2") (pintype "bidirectional"))
      (node (ref "U70") (pin "VIN") (pinfunction "VIN_VIN") (pintype "bidirectional"))
    )
    (net (code "82") (name "XBEEDIN") (class "Default")
      (node (ref "P1") (pin "P14") (pinfunction "P14_P14") (pintype "bidirectional"))
      (node (ref "U$19") (pin "3") (pinfunction "DIN/D14_3") (pintype "bidirectional"))
      (node (ref "XBEE_DIN") (pin "1") (pinfunction "1_1") (pintype "bidirectional"))
    )
    (net (code "83") (name "XBEEDOUT") (class "Default")
      (node (ref "P1") (pin "P15") (pinfunction "P15_P15") (pintype "bidirectional"))
      (node (ref "U$19") (pin "2") (pinfunction "DOUT/D13_2") (pintype "bidirectional"))
      (node (ref "XBEE_DOUT") (pin "1") (pinfunction "1_1") (pintype "bidirectional"))
    )
    (net (code "84") (name "unconnected-(J5-RING2-Pad4-1)") (class "Default")
      (node (ref "J5") (pin "4-1") (pinfunction "RING2_4-1") (pintype "bidirectional"))
    )
    (net (code "85") (name "unconnected-(P2-Pad5V)") (class "Default")
      (node (ref "P2") (pin "5V") (pinfunction "5V_5V") (pintype "bidirectional"))
    )
    (net (code "86") (name "unconnected-(U$19-D0-Pad20)") (class "Default")
      (node (ref "U$19") (pin "20") (pinfunction "D0_20") (pintype "bidirectional"))
    )
    (net (code "87") (name "unconnected-(U$19-D1-Pad19)") (class "Default")
      (node (ref "U$19") (pin "19") (pinfunction "D1_19") (pintype "bidirectional"))
    )
    (net (code "88") (name "unconnected-(U$19-D2-Pad18)") (class "Default")
      (node (ref "U$19") (pin "18") (pinfunction "D2_18") (pintype "bidirectional"))
    )
    (net (code "89") (name "unconnected-(U$19-D3-Pad17)") (class "Default")
      (node (ref "U$19") (pin "17") (pinfunction "D3_17") (pintype "bidirectional"))
    )
    (net (code "90") (name "unconnected-(U$19-D4-Pad11)") (class "Default")
      (node (ref "U$19") (pin "11") (pinfunction "D4_11") (pintype "bidirectional"))
    )
    (net (code "91") (name "unconnected-(U$19-D6-Pad16)") (class "Default")
      (node (ref "U$19") (pin "16") (pinfunction "D6_16") (pintype "bidirectional"))
    )
    (net (code "92") (name "unconnected-(U$19-D7-Pad12)") (class "Default")
      (node (ref "U$19") (pin "12") (pinfunction "D7_12") (pintype "bidirectional"))
    )
    (net (code "93") (name "unconnected-(U$19-D8-Pad9)") (class "Default")
      (node (ref "U$19") (pin "9") (pinfunction "D8_9") (pintype "bidirectional"))
    )
    (net (code "94") (name "unconnected-(U$19-D9-Pad13)") (class "Default")
      (node (ref "U$19") (pin "13") (pinfunction "D9_13") (pintype "bidirectional"))
    )
    (net (code "95") (name "unconnected-(U$19-D11-Pad7)") (class "Default")
      (node (ref "U$19") (pin "7") (pinfunction "D11_7") (pintype "bidirectional"))
    )
    (net (code "96") (name "unconnected-(U$19-D12-Pad4)") (class "Default")
      (node (ref "U$19") (pin "4") (pinfunction "D12_4") (pintype "bidirectional"))
    )
    (net (code "97") (name "unconnected-(U$19-NC-Pad8)") (class "Default")
      (node (ref "U$19") (pin "8") (pinfunction "NC_8") (pintype "bidirectional"))
    )
    (net (code "98") (name "unconnected-(U$19-VREF{slash}NC-Pad14)") (class "Default")
      (node (ref "U$19") (pin "14") (pinfunction "VREF/NC_14") (pintype "bidirectional"))
    )
    (net (code "99") (name "unconnected-(U2-IN2-Pad3)") (class "Default")
      (node (ref "U2") (pin "3") (pinfunction "IN2_3") (pintype "bidirectional"))
    )
    (net (code "100") (name "unconnected-(U2-NC-Pad1)") (class "Default")
      (node (ref "U2") (pin "1") (pinfunction "NC_1") (pintype "bidirectional"))
    )
    (net (code "101") (name "unconnected-(U2-OUT2-Pad6)") (class "Default")
      (node (ref "U2") (pin "6") (pinfunction "OUT2_6") (pintype "bidirectional"))
    )
    (net (code "102") (name "unconnected-(U4-BP-Pad4)") (class "Default")
      (node (ref "U4") (pin "4") (pinfunction "BP_4") (pintype "input"))
    )
    (net (code "103") (name "unconnected-(U70-NC1-PadNC)") (class "Default")
      (node (ref "U70") (pin "NC") (pinfunction "NC1_NC") (pintype "bidirectional"))
    )
    (net (code "104") (name "unconnected-(U70-PadNC2)") (class "Default")
      (node (ref "U70") (pin "NC2") (pinfunction "NC2_NC2") (pintype "bidirectional"))
    )
  )
)
